# TS5A23166DCUR_breakout.net
KiCad netlist of a schematic drawn in EAGLE
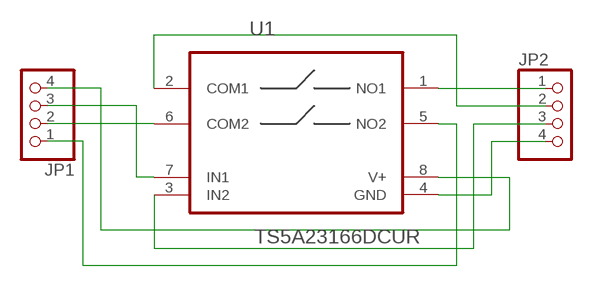
[diagram p0: schematic, sheet 1]

(export (version "E")
  (design (tool "Eeschema 10.0.6"))
  (components
    (comp (ref "JP1")
      (value "PINHD-1X4")
      (footprint "eagle-import:1X04")
      (libsource (lib "eagle-import") (part "PINHD-1X4"))
    )
    (comp (ref "JP2")
      (value "PINHD-1X4")
      (footprint "eagle-import:1X04")
      (libsource (lib "eagle-import") (part "PINHD-1X4"))
    )
    (comp (ref "U1")
      (value "TS5A23166DCUR")
      (footprint "eagle-import:SOP50P310X90-8N")
      (fields (field (name "MF") "Texas Instruments"))
      (libsource (lib "eagle-import") (part "TS5A23166DCUR"))
    )
  )
  (nets
    (net (code "1") (name "Net-(U1-COM1)") (class "Default")
      (node (ref "JP2") (pin "2") (pinfunction "2_2") (pintype "passive"))
      (node (ref "U1") (pin "2") (pinfunction "COM1_2") (pintype "bidirectional"))
    )
    (net (code "2") (name "Net-(U1-COM2)") (class "Default")
      (node (ref "JP1") (pin "2") (pinfunction "2_2") (pintype "passive"))
      (node (ref "U1") (pin "6") (pinfunction "COM2_6") (pintype "bidirectional"))
    )
    (net (code "3") (name "Net-(U1-GND)") (class "Default")
      (node (ref "JP2") (pin "4") (pinfunction "4_4") (pintype "passive"))
      (node (ref "U1") (pin "4") (pinfunction "GND_4") (pintype "passive"))
    )
    (net (code "4") (name "Net-(U1-IN1)") (class "Default")
      (node (ref "JP1") (pin "3") (pinfunction "3_3") (pintype "passive"))
      (node (ref "U1") (pin "7") (pinfunction "IN1_7") (pintype "input"))
    )
    (net (code "5") (name "Net-(U1-IN2)") (class "Default")
      (node (ref "JP2") (pin "3") (pinfunction "3_3") (pintype "passive"))
      (node (ref "U1") (pin "3") (pinfunction "IN2_3") (pintype "input"))
    )
    (net (code "6") (name "Net-(U1-NO1)") (class "Default")
      (node (ref "JP2") (pin "1") (pinfunction "1_1") (pintype "passive"))
      (node (ref "U1") (pin "1") (pinfunction "NO1_1") (pintype "bidirectional"))
    )
    (net (code "7") (name "Net-(U1-NO2)") (class "Default")
      (node (ref "JP1") (pin "1") (pinfunction "1_1") (pintype "passive"))
      (node (ref "U1") (pin "5") (pinfunction "NO2_5") (pintype "bidirectional"))
    )
    (net (code "8") (name "Net-(U1-V+)") (class "Default")
      (node (ref "JP1") (pin "4") (pinfunction "4_4") (pintype "passive"))
      (node (ref "U1") (pin "8") (pinfunction "V+_8") (pintype "power_in"))
    )
  )
)
